# ARE_adaptadores_final.net
KiCad netlist of a schematic drawn in EAGLE
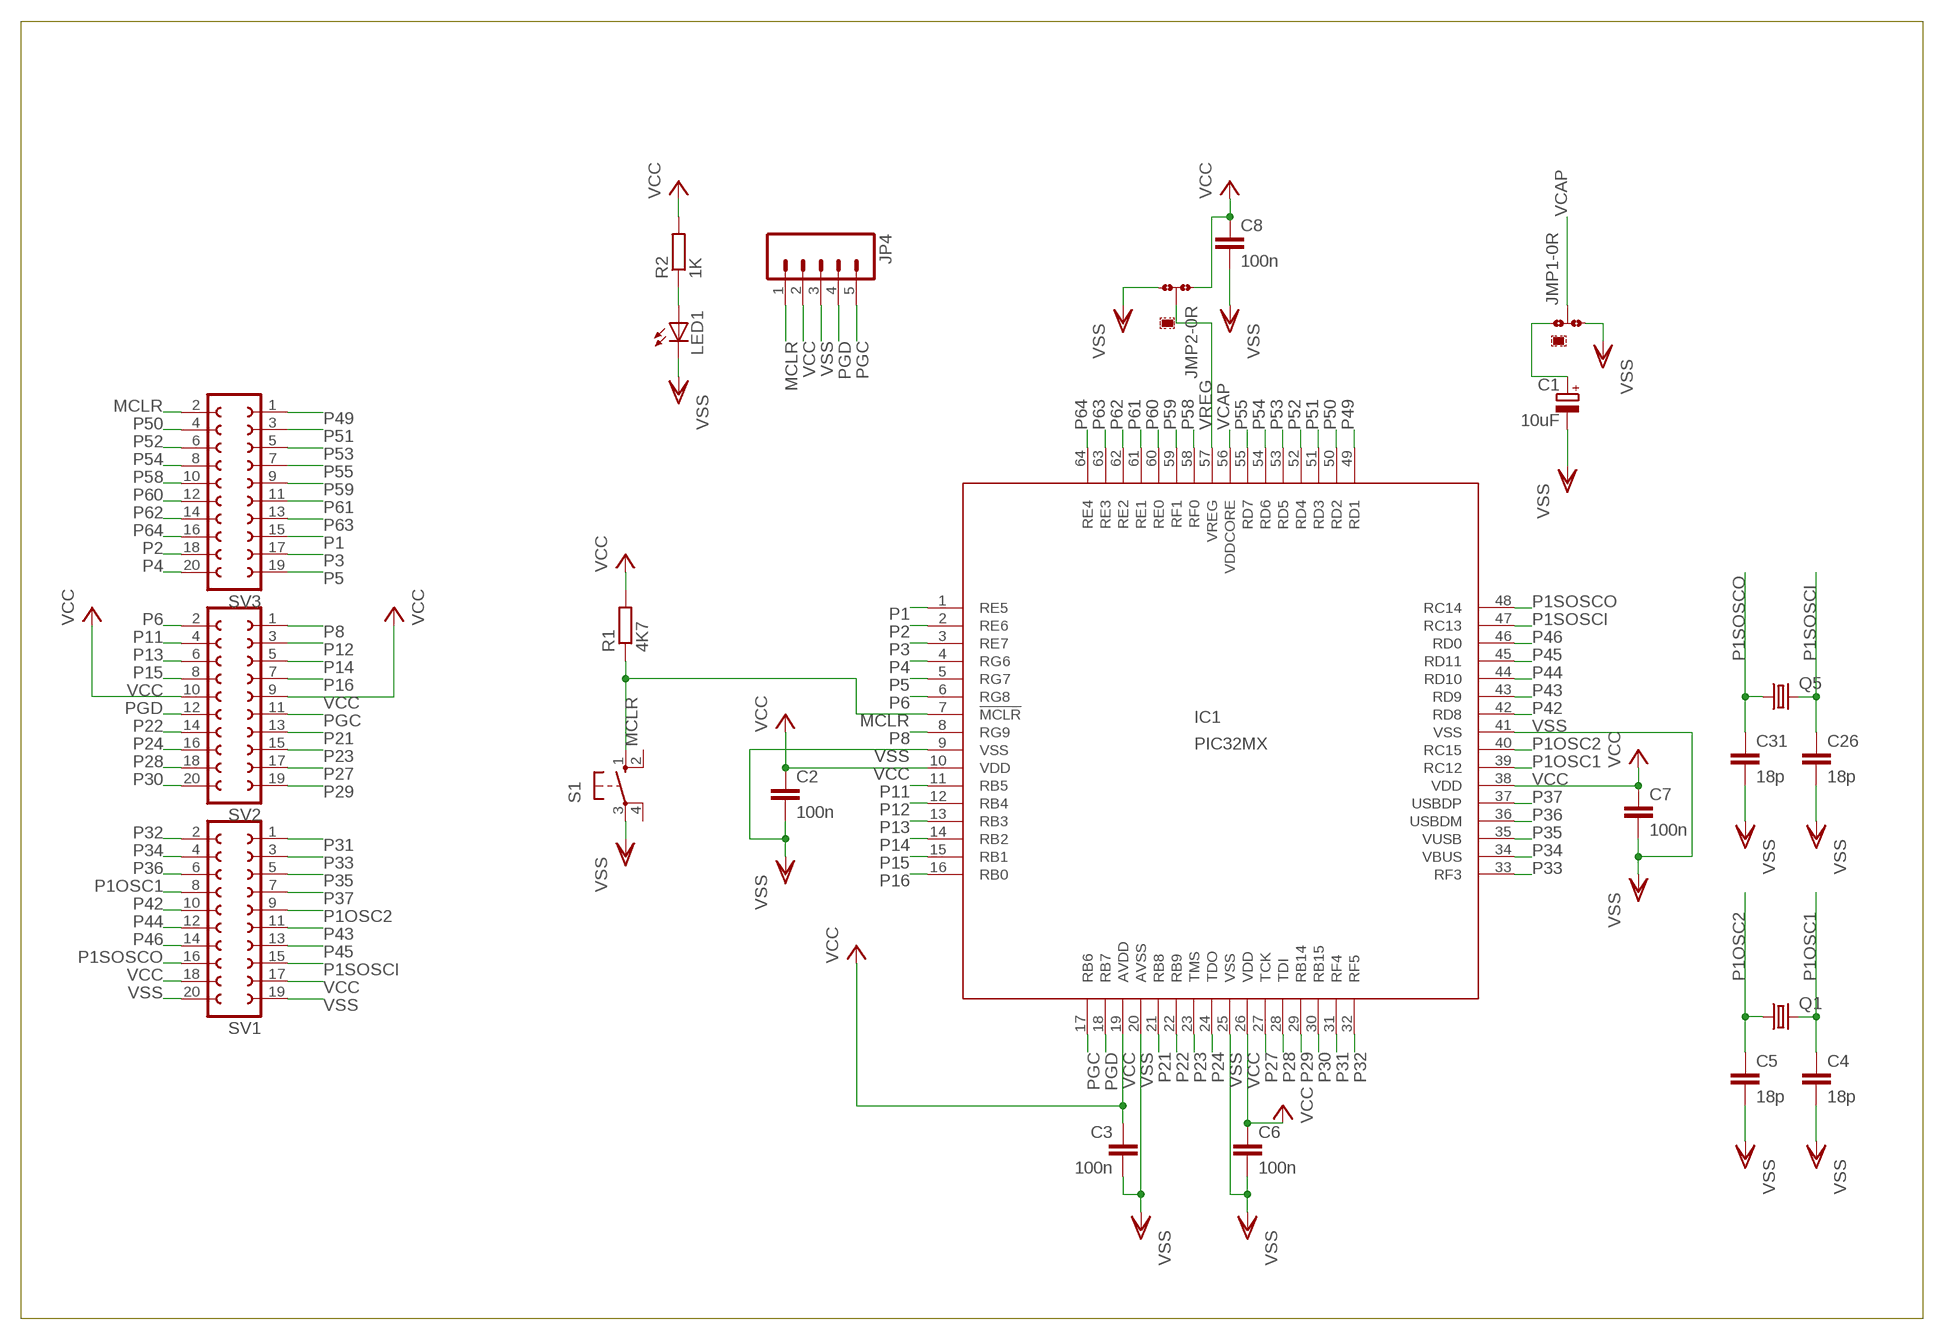
[diagram p0: schematic, sheet 1]
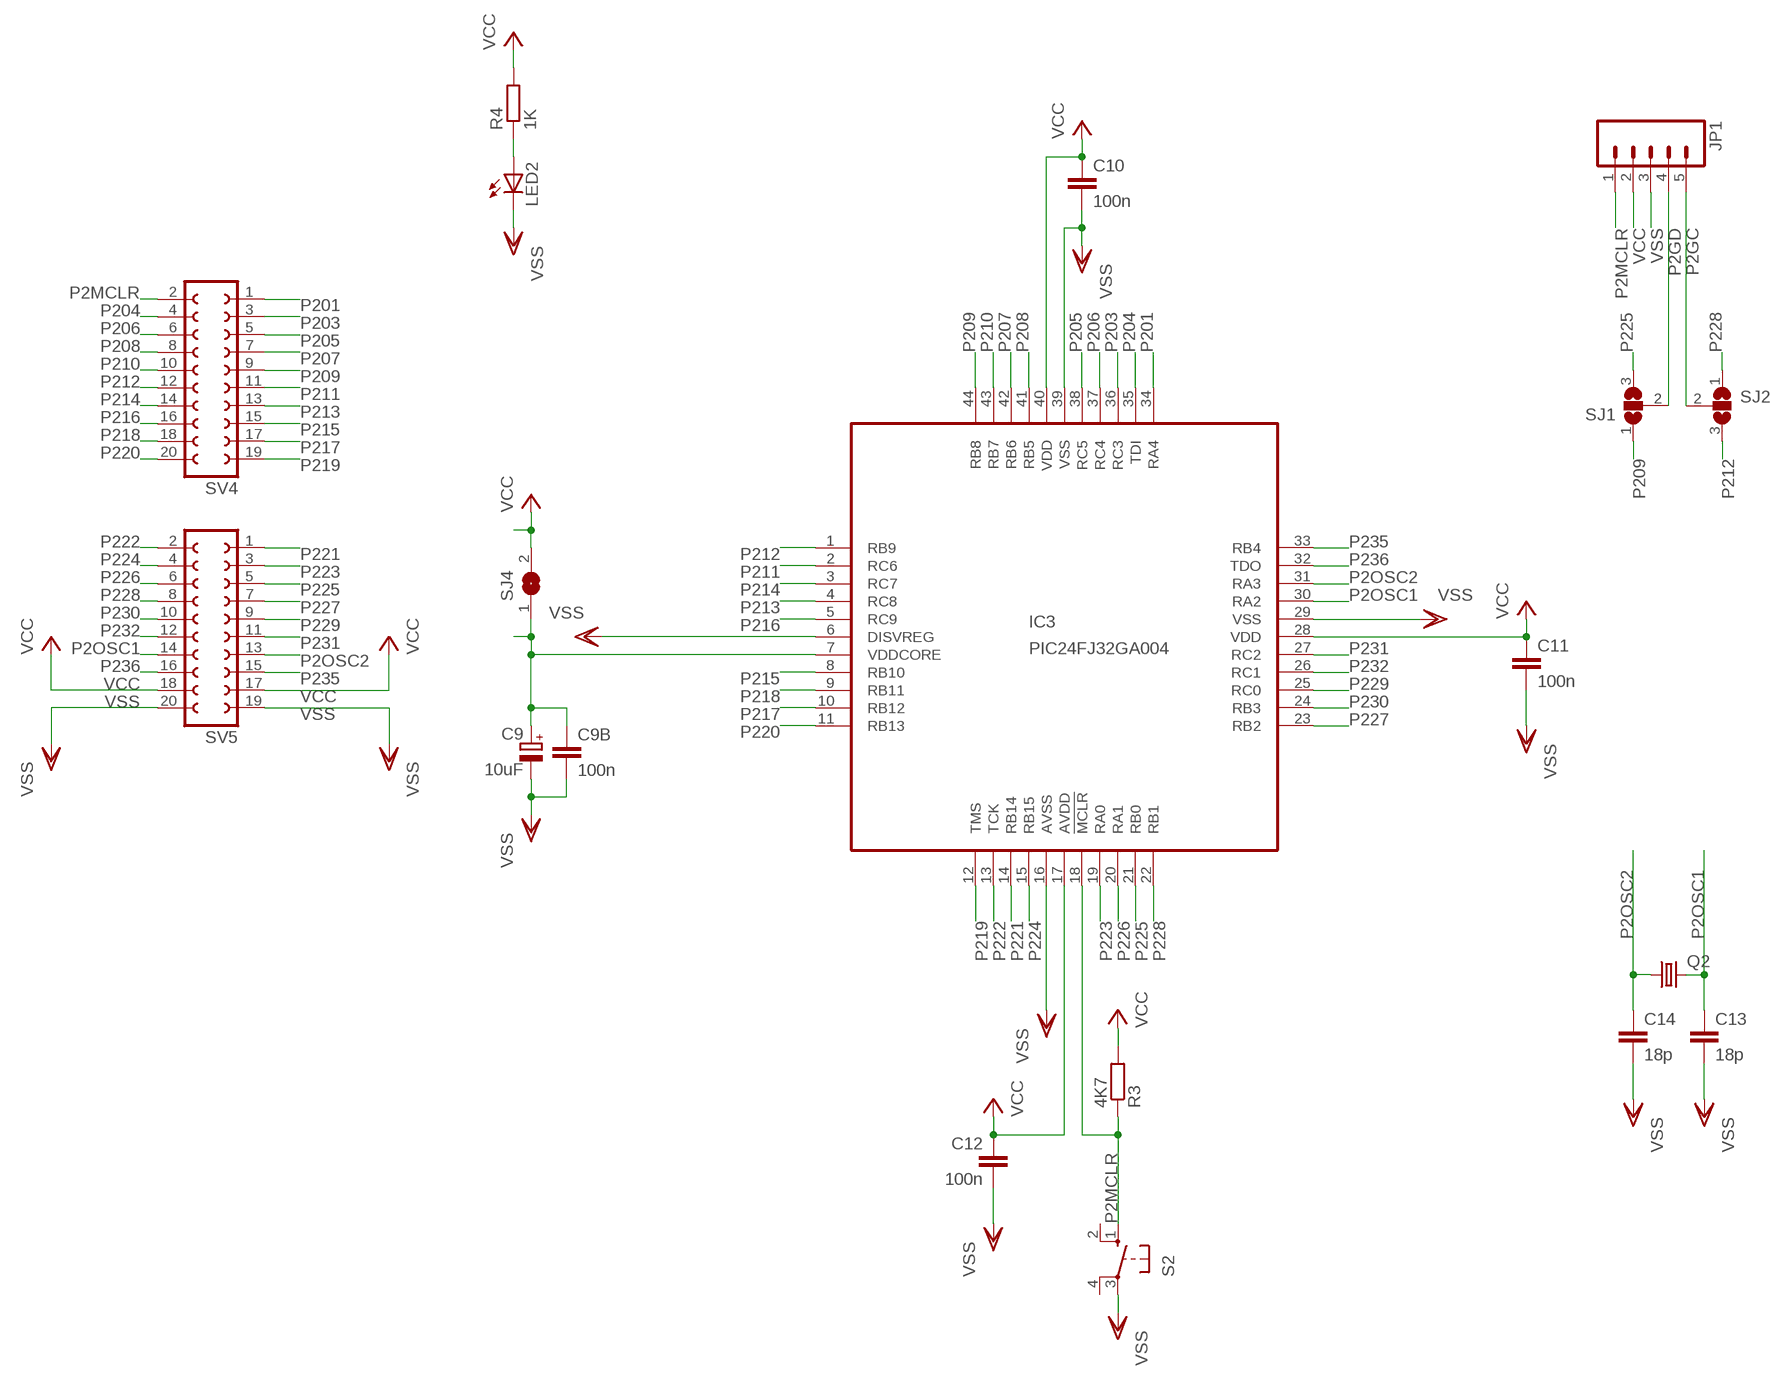
[diagram p1: schematic, sheet 2]
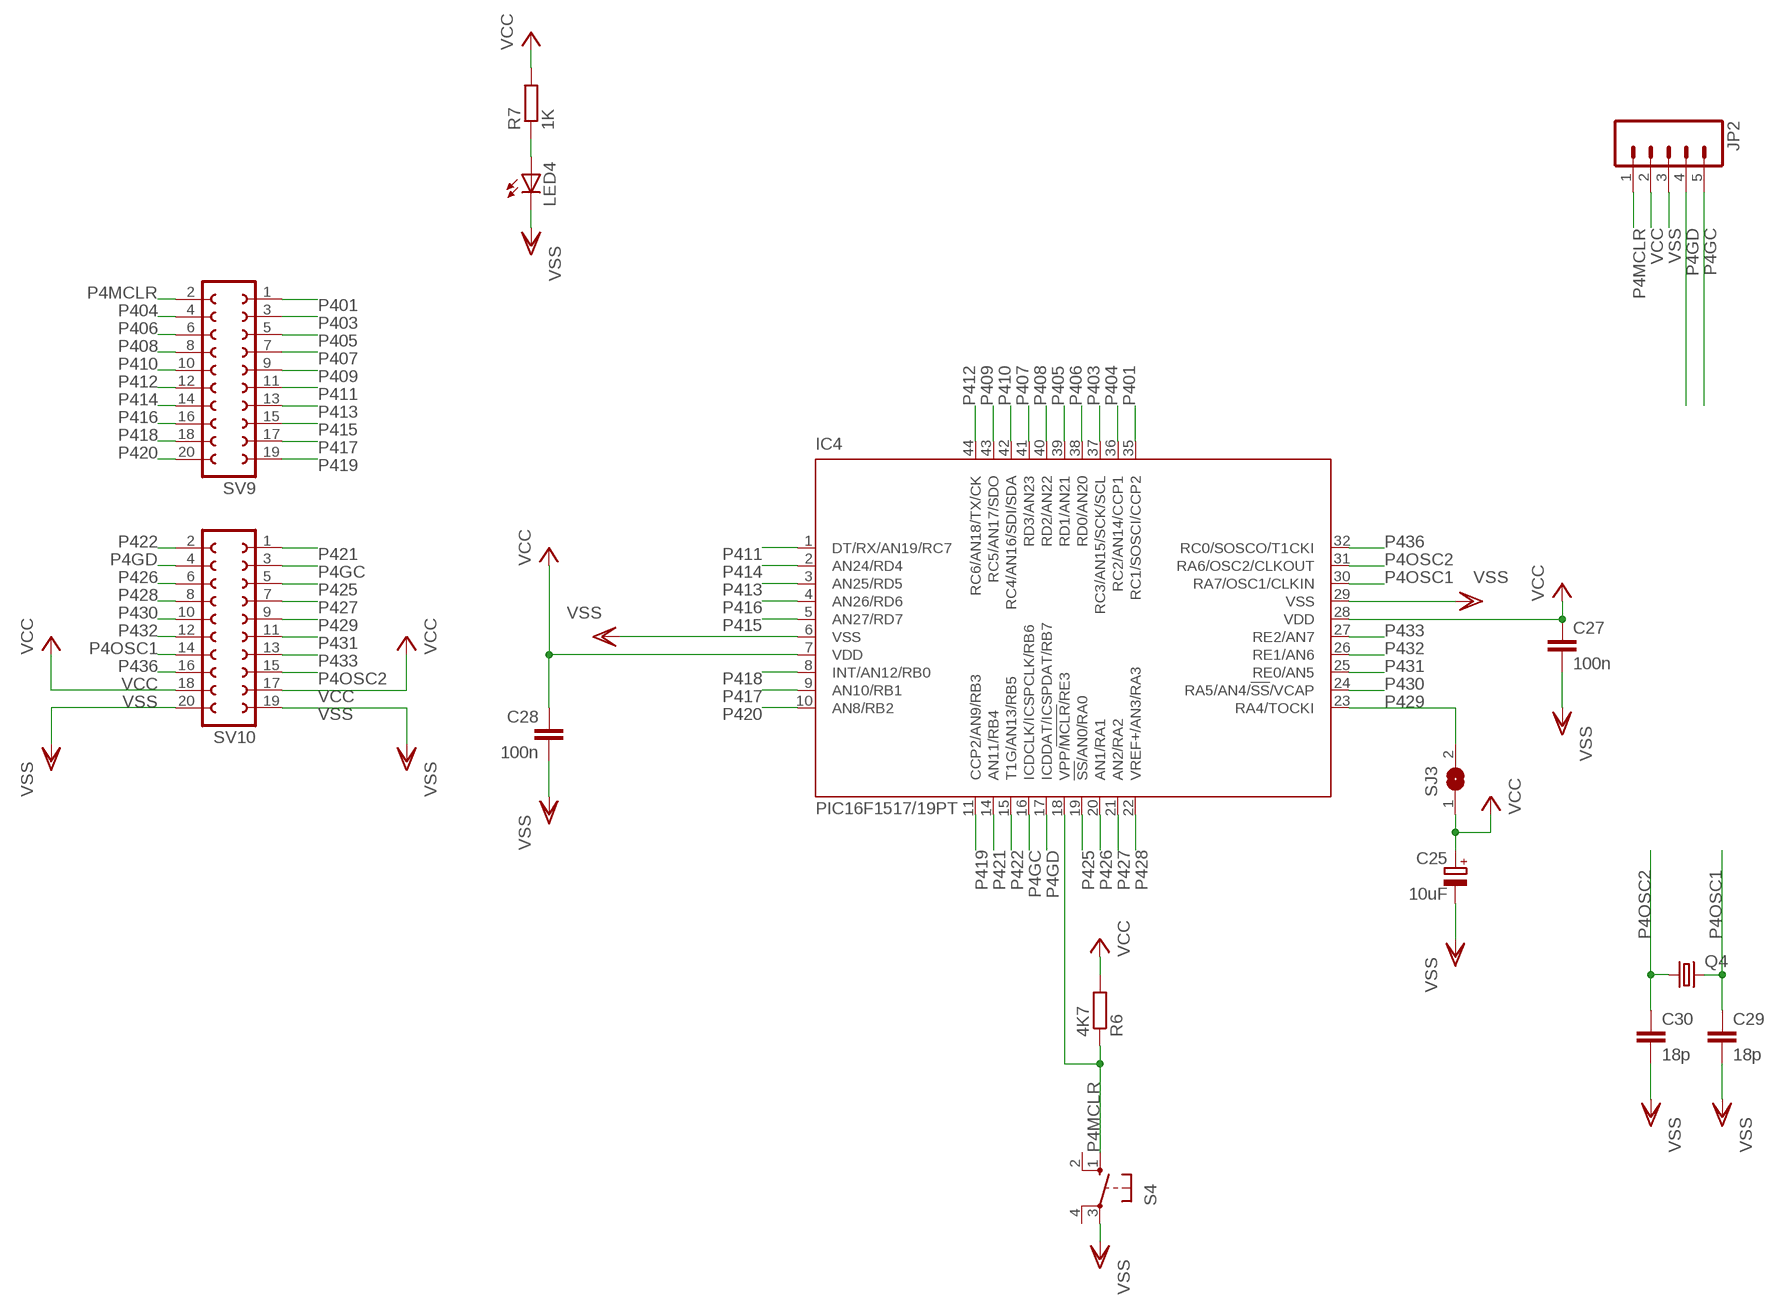
[diagram p2: schematic, sheet 3]
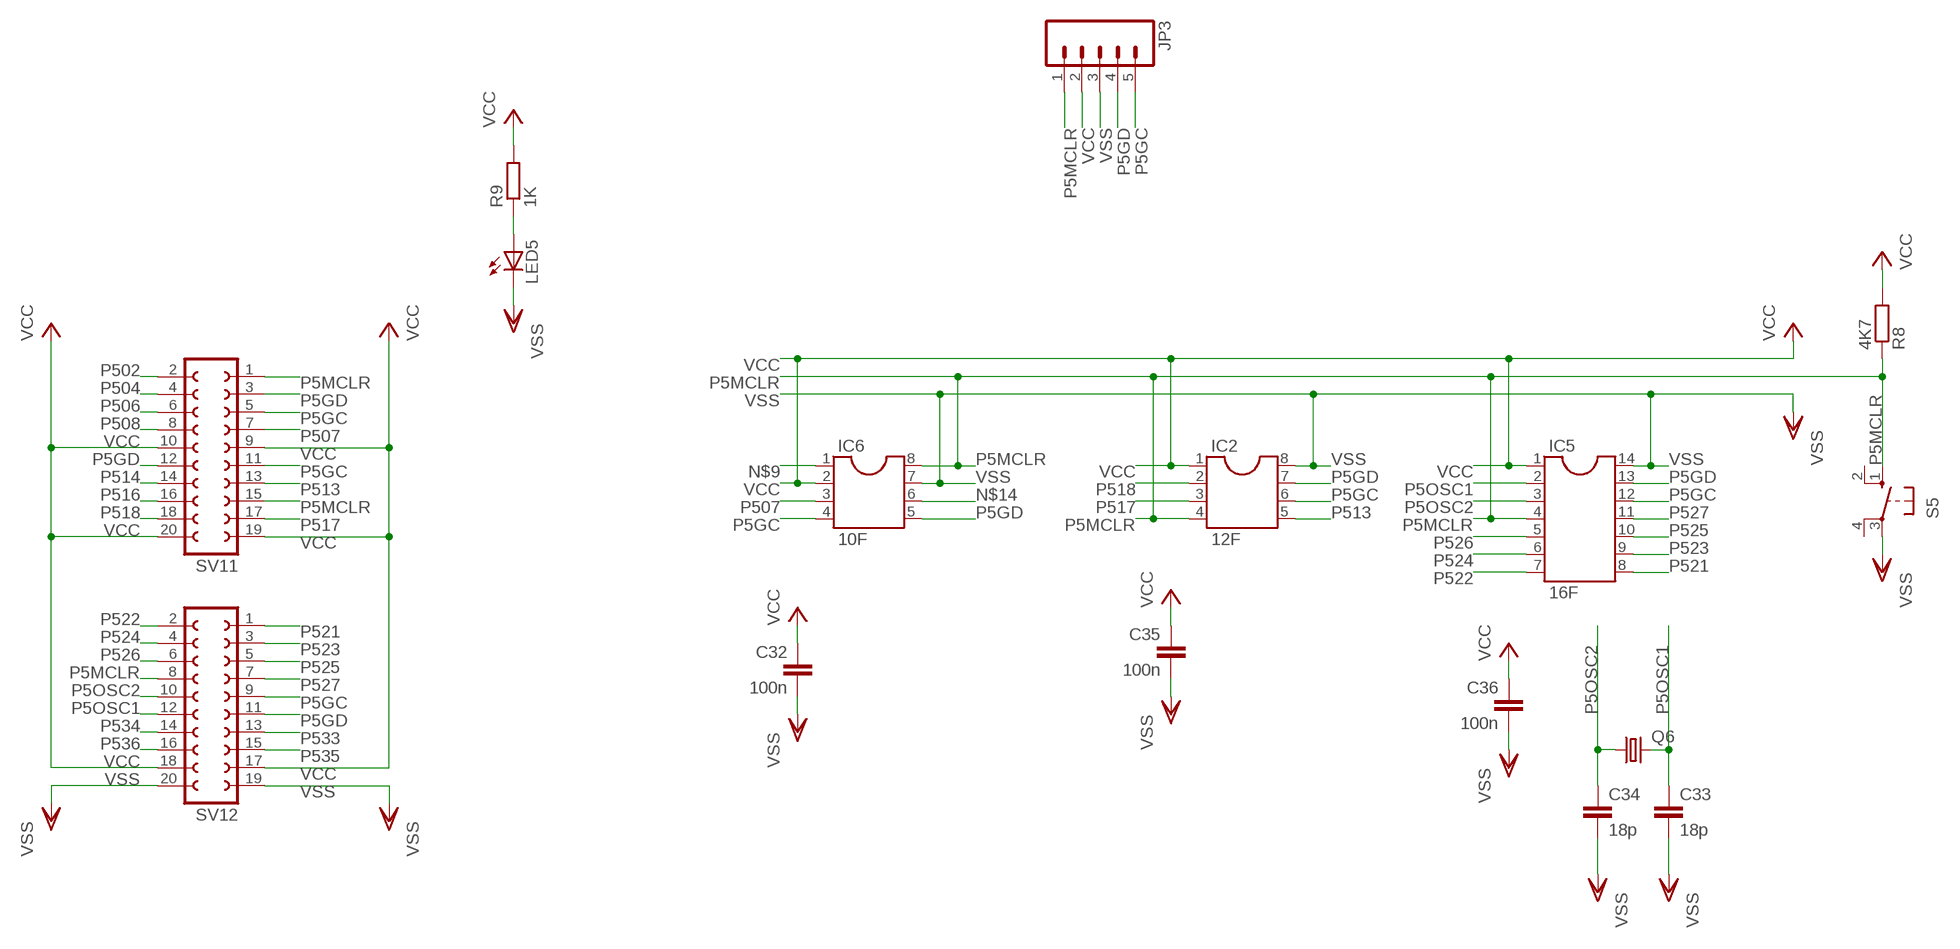
[diagram p3: schematic, sheet 4]

(export (version "E")
  (design (tool "Eeschema 10.0.6"))
  (components
    (comp (ref "C1")
      (value "10uF")
      (footprint "eagle-import:SMC_C")
      (libsource (lib "eagle-import") (part "CPOL-EUSMCC"))
    )
    (comp (ref "C2")
      (value "100n")
      (footprint "eagle-import:C0805")
      (libsource (lib "eagle-import") (part "C-EUC0805"))
    )
    (comp (ref "C3")
      (value "100n")
      (footprint "eagle-import:C0805")
      (libsource (lib "eagle-import") (part "C-EUC0805"))
    )
    (comp (ref "C4")
      (value "18p")
      (footprint "eagle-import:C0805")
      (libsource (lib "eagle-import") (part "C-EUC0805"))
    )
    (comp (ref "C5")
      (value "18p")
      (footprint "eagle-import:C0805")
      (libsource (lib "eagle-import") (part "C-EUC0805"))
    )
    (comp (ref "C6")
      (value "100n")
      (footprint "eagle-import:C0805")
      (libsource (lib "eagle-import") (part "C-EUC0805"))
    )
    (comp (ref "C7")
      (value "100n")
      (footprint "eagle-import:C0805")
      (libsource (lib "eagle-import") (part "C-EUC0805"))
    )
    (comp (ref "C8")
      (value "100n")
      (footprint "eagle-import:C0805")
      (libsource (lib "eagle-import") (part "C-EUC0805"))
    )
    (comp (ref "C26")
      (value "18p")
      (footprint "eagle-import:C0805")
      (libsource (lib "eagle-import") (part "C-EUC0805"))
    )
    (comp (ref "C31")
      (value "18p")
      (footprint "eagle-import:C0805")
      (libsource (lib "eagle-import") (part "C-EUC0805"))
    )
    (comp (ref "IC1")
      (value "PIC32MX")
      (footprint "eagle-import:TQFP64-10X10")
      (libsource (lib "eagle-import") (part "PIC32MX440F256H"))
    )
    (comp (ref "JMP1")
      (value "0R-JUMPA")
      (footprint "eagle-import:A0R-JMP")
      (libsource (lib "eagle-import") (part "0R-JUMPA"))
    )
    (comp (ref "JMP2")
      (value "0R-JUMPA")
      (footprint "eagle-import:A0R-JMP")
      (libsource (lib "eagle-import") (part "0R-JUMPA"))
    )
    (comp (ref "JP4")
      (value "M05PTH")
      (footprint "eagle-import:1X05")
      (libsource (lib "eagle-import") (part "M05PTH"))
    )
    (comp (ref "LED1")
      (value "LEDCHIPLED_0805")
      (footprint "eagle-import:CHIPLED_0805")
      (libsource (lib "eagle-import") (part "LEDCHIPLED_0805"))
    )
    (comp (ref "Q1")
      (value "CRYSTALHC18U-V")
      (footprint "eagle-import:HC18U-V")
      (libsource (lib "eagle-import") (part "CRYSTALHC18U-V"))
    )
    (comp (ref "Q5")
      (value "CRYSTALHC18U-V")
      (footprint "eagle-import:HC18U-V")
      (libsource (lib "eagle-import") (part "CRYSTALHC18U-V"))
    )
    (comp (ref "R1")
      (value "4K7")
      (footprint "eagle-import:R0805")
      (libsource (lib "eagle-import") (part "R-EU_R0805"))
    )
    (comp (ref "R2")
      (value "1K")
      (footprint "eagle-import:R0805")
      (libsource (lib "eagle-import") (part "R-EU_R0805"))
    )
    (comp (ref "S1")
      (value "10-XX")
      (footprint "eagle-import:B3F-10XX")
      (fields
        (field (name "MPN") "B3F-1000")
        (field (name "MPN_1") "B3F-1000")
        (field (name "OC_FARNELL") "176432")
        (field (name "OC_NEWARK") "36M3542")
      )
      (libsource (lib "eagle-import") (part "10-XX"))
    )
    (comp (ref "SV1")
      (value "FE10-2W")
      (footprint "eagle-import:FE10-2W")
      (libsource (lib "eagle-import") (part "FE10-2W"))
    )
    (comp (ref "SV2")
      (value "FE10-2W")
      (footprint "eagle-import:FE10-2W")
      (libsource (lib "eagle-import") (part "FE10-2W"))
    )
    (comp (ref "SV3")
      (value "FE10-2W")
      (footprint "eagle-import:FE10-2W")
      (libsource (lib "eagle-import") (part "FE10-2W"))
    )
    (comp (ref "C25")
      (value "10uF")
      (footprint "eagle-import:SMC_C")
      (libsource (lib "eagle-import") (part "CPOL-EUSMCC"))
    )
    (comp (ref "C27")
      (value "100n")
      (footprint "eagle-import:C0805")
      (libsource (lib "eagle-import") (part "C-EUC0805"))
    )
    (comp (ref "C28")
      (value "100n")
      (footprint "eagle-import:C0805")
      (libsource (lib "eagle-import") (part "C-EUC0805"))
    )
    (comp (ref "C29")
      (value "18p")
      (footprint "eagle-import:C0805")
      (libsource (lib "eagle-import") (part "C-EUC0805"))
    )
    (comp (ref "C30")
      (value "18p")
      (footprint "eagle-import:C0805")
      (libsource (lib "eagle-import") (part "C-EUC0805"))
    )
    (comp (ref "IC4")
      (value "PIC16F1517/19PT")
      (footprint "eagle-import:TQFP44")
      (libsource (lib "eagle-import") (part "PIC16F1517/19PT"))
    )
    (comp (ref "JP2")
      (value "M05PTH")
      (footprint "eagle-import:1X05")
      (libsource (lib "eagle-import") (part "M05PTH"))
    )
    (comp (ref "LED4")
      (value "LEDCHIPLED_0805")
      (footprint "eagle-import:CHIPLED_0805")
      (libsource (lib "eagle-import") (part "LEDCHIPLED_0805"))
    )
    (comp (ref "Q4")
      (value "CRYSTALHC18U-V")
      (footprint "eagle-import:HC18U-V")
      (libsource (lib "eagle-import") (part "CRYSTALHC18U-V"))
    )
    (comp (ref "R6")
      (value "4K7")
      (footprint "eagle-import:R0805")
      (libsource (lib "eagle-import") (part "R-EU_R0805"))
    )
    (comp (ref "R7")
      (value "1K")
      (footprint "eagle-import:R0805")
      (libsource (lib "eagle-import") (part "R-EU_R0805"))
    )
    (comp (ref "S4")
      (value "10-XX")
      (footprint "eagle-import:B3F-10XX")
      (fields
        (field (name "MPN") "B3F-1000")
        (field (name "MPN_1") "B3F-1000")
        (field (name "OC_FARNELL") "176432")
        (field (name "OC_NEWARK") "36M3542")
      )
      (libsource (lib "eagle-import") (part "10-XX"))
    )
    (comp (ref "SJ3") (value "SJ") (footprint "eagle-import:SJ") (libsource (lib "eagle-import") (part "SJ")))
    (comp (ref "SV9")
      (value "FE10-2W")
      (footprint "eagle-import:FE10-2W")
      (libsource (lib "eagle-import") (part "FE10-2W"))
    )
    (comp (ref "SV10")
      (value "FE10-2W")
      (footprint "eagle-import:FE10-2W")
      (libsource (lib "eagle-import") (part "FE10-2W"))
    )
    (comp (ref "C32")
      (value "100n")
      (footprint "eagle-import:C0805")
      (libsource (lib "eagle-import") (part "C-EUC0805"))
    )
    (comp (ref "C33")
      (value "18p")
      (footprint "eagle-import:C0805")
      (libsource (lib "eagle-import") (part "C-EUC0805"))
    )
    (comp (ref "C34")
      (value "18p")
      (footprint "eagle-import:C0805")
      (libsource (lib "eagle-import") (part "C-EUC0805"))
    )
    (comp (ref "C35")
      (value "100n")
      (footprint "eagle-import:C0805")
      (libsource (lib "eagle-import") (part "C-EUC0805"))
    )
    (comp (ref "C36")
      (value "100n")
      (footprint "eagle-import:C0805")
      (libsource (lib "eagle-import") (part "C-EUC0805"))
    )
    (comp (ref "IC2")
      (value "12F")
      (footprint "eagle-import:SOCKET-08")
      (libsource (lib "eagle-import") (part "DIL8S"))
    )
    (comp (ref "IC5")
      (value "16F")
      (footprint "eagle-import:SOCKET-14")
      (libsource (lib "eagle-import") (part "DIL14S"))
    )
    (comp (ref "IC6")
      (value "10F")
      (footprint "eagle-import:SOCKET-08")
      (libsource (lib "eagle-import") (part "DIL8S"))
    )
    (comp (ref "JP3")
      (value "M05PTH")
      (footprint "eagle-import:1X05")
      (libsource (lib "eagle-import") (part "M05PTH"))
    )
    (comp (ref "LED5")
      (value "LEDCHIPLED_0805")
      (footprint "eagle-import:CHIPLED_0805")
      (libsource (lib "eagle-import") (part "LEDCHIPLED_0805"))
    )
    (comp (ref "Q6")
      (value "CRYSTALHC18U-V")
      (footprint "eagle-import:HC18U-V")
      (libsource (lib "eagle-import") (part "CRYSTALHC18U-V"))
    )
    (comp (ref "R8")
      (value "4K7")
      (footprint "eagle-import:R0805")
      (libsource (lib "eagle-import") (part "R-EU_R0805"))
    )
    (comp (ref "R9")
      (value "1K")
      (footprint "eagle-import:R0805")
      (libsource (lib "eagle-import") (part "R-EU_R0805"))
    )
    (comp (ref "S5")
      (value "10-XX")
      (footprint "eagle-import:B3F-10XX")
      (fields
        (field (name "MPN") "B3F-1000")
        (field (name "MPN_1") "B3F-1000")
        (field (name "OC_FARNELL") "176432")
        (field (name "OC_NEWARK") "36M3542")
      )
      (libsource (lib "eagle-import") (part "10-XX"))
    )
    (comp (ref "SV11")
      (value "FE10-2W")
      (footprint "eagle-import:FE10-2W")
      (libsource (lib "eagle-import") (part "FE10-2W"))
    )
    (comp (ref "SV12")
      (value "FE10-2W")
      (footprint "eagle-import:FE10-2W")
      (libsource (lib "eagle-import") (part "FE10-2W"))
    )
    (comp (ref "C9")
      (value "10uF")
      (footprint "eagle-import:SMC_C")
      (libsource (lib "eagle-import") (part "CPOL-EUSMCC"))
    )
    (comp (ref "C9B")
      (value "100n")
      (footprint "eagle-import:C0805")
      (libsource (lib "eagle-import") (part "C-EUC0805"))
    )
    (comp (ref "C10")
      (value "100n")
      (footprint "eagle-import:C0805")
      (libsource (lib "eagle-import") (part "C-EUC0805"))
    )
    (comp (ref "C11")
      (value "100n")
      (footprint "eagle-import:C0805")
      (libsource (lib "eagle-import") (part "C-EUC0805"))
    )
    (comp (ref "C12")
      (value "100n")
      (footprint "eagle-import:C0805")
      (libsource (lib "eagle-import") (part "C-EUC0805"))
    )
    (comp (ref "C13")
      (value "18p")
      (footprint "eagle-import:C0805")
      (libsource (lib "eagle-import") (part "C-EUC0805"))
    )
    (comp (ref "C14")
      (value "18p")
      (footprint "eagle-import:C0805")
      (libsource (lib "eagle-import") (part "C-EUC0805"))
    )
    (comp (ref "IC3")
      (value "PIC24FJ32GA004")
      (footprint "eagle-import:TQFP44")
      (fields (field (name "MPN") "PIC24FJ32GA004-E/PT"))
      (libsource (lib "eagle-import") (part "PIC24FJ32GA004"))
    )
    (comp (ref "JP1")
      (value "M05PTH")
      (footprint "eagle-import:1X05")
      (libsource (lib "eagle-import") (part "M05PTH"))
    )
    (comp (ref "LED2")
      (value "LEDCHIPLED_0805")
      (footprint "eagle-import:CHIPLED_0805")
      (libsource (lib "eagle-import") (part "LEDCHIPLED_0805"))
    )
    (comp (ref "Q2")
      (value "CRYSTALHC18U-V")
      (footprint "eagle-import:HC18U-V")
      (libsource (lib "eagle-import") (part "CRYSTALHC18U-V"))
    )
    (comp (ref "R3")
      (value "4K7")
      (footprint "eagle-import:R0805")
      (libsource (lib "eagle-import") (part "R-EU_R0805"))
    )
    (comp (ref "R4")
      (value "1K")
      (footprint "eagle-import:R0805")
      (libsource (lib "eagle-import") (part "R-EU_R0805"))
    )
    (comp (ref "S2")
      (value "10-XX")
      (footprint "eagle-import:B3F-10XX")
      (fields
        (field (name "MPN") "B3F-1000")
        (field (name "MPN_1") "B3F-1000")
        (field (name "OC_FARNELL") "176432")
        (field (name "OC_NEWARK") "36M3542")
      )
      (libsource (lib "eagle-import") (part "10-XX"))
    )
    (comp (ref "SJ1")
      (value "SJ2W")
      (footprint "eagle-import:SJ_2")
      (libsource (lib "eagle-import") (part "SJ2W"))
    )
    (comp (ref "SJ2")
      (value "SJ2W")
      (footprint "eagle-import:SJ_2")
      (libsource (lib "eagle-import") (part "SJ2W"))
    )
    (comp (ref "SJ4") (value "SJ") (footprint "eagle-import:SJ") (libsource (lib "eagle-import") (part "SJ")))
    (comp (ref "SV4")
      (value "FE10-2W")
      (footprint "eagle-import:FE10-2W")
      (libsource (lib "eagle-import") (part "FE10-2W"))
    )
    (comp (ref "SV5")
      (value "FE10-2W")
      (footprint "eagle-import:FE10-2W")
      (libsource (lib "eagle-import") (part "FE10-2W"))
    )
  )
  (nets
    (net (code "1") (name "MCLR") (class "Default")
      (node (ref "IC1") (pin "7") (pinfunction "~{MCLR}_7") (pintype "input"))
      (node (ref "JP4") (pin "1") (pinfunction "1_1") (pintype "passive"))
      (node (ref "R1") (pin "1") (pinfunction "1_1") (pintype "passive"))
      (node (ref "S1") (pin "1") (pinfunction "S_1") (pintype "passive"))
      (node (ref "SV3") (pin "2") (pinfunction "2_2") (pintype "passive"))
    )
    (net (code "2") (name "N$9") (class "Default")
      (node (ref "IC6") (pin "1") (pinfunction "1_1") (pintype "passive"))
    )
    (net (code "3") (name "N$14") (class "Default")
      (node (ref "IC6") (pin "6") (pinfunction "6_6") (pintype "passive"))
    )
    (net (code "4") (name "Net-(C1-Pad+)") (class "Default")
      (node (ref "C1") (pin "+") (pinfunction "+_+") (pintype "passive"))
      (node (ref "JMP1") (pin "1") (pinfunction "1_1") (pintype "passive"))
    )
    (net (code "5") (name "Net-(IC3-VDDCORE)") (class "Default")
      (node (ref "C9") (pin "+") (pinfunction "+_+") (pintype "passive"))
      (node (ref "C9B") (pin "1") (pinfunction "1_1") (pintype "passive"))
      (node (ref "IC3") (pin "7") (pinfunction "VDDCORE_7") (pintype "power_in"))
      (node (ref "SJ4") (pin "1") (pinfunction "1_1") (pintype "passive"))
    )
    (net (code "6") (name "Net-(LED1-PadA)") (class "Default")
      (node (ref "LED1") (pin "A") (pinfunction "A_A") (pintype "passive"))
      (node (ref "R2") (pin "1") (pinfunction "1_1") (pintype "passive"))
    )
    (net (code "7") (name "Net-(LED2-PadA)") (class "Default")
      (node (ref "LED2") (pin "A") (pinfunction "A_A") (pintype "passive"))
      (node (ref "R4") (pin "1") (pinfunction "1_1") (pintype "passive"))
    )
    (net (code "8") (name "Net-(LED4-PadA)") (class "Default")
      (node (ref "LED4") (pin "A") (pinfunction "A_A") (pintype "passive"))
      (node (ref "R7") (pin "1") (pinfunction "1_1") (pintype "passive"))
    )
    (net (code "9") (name "Net-(LED5-PadA)") (class "Default")
      (node (ref "LED5") (pin "A") (pinfunction "A_A") (pintype "passive"))
      (node (ref "R9") (pin "1") (pinfunction "1_1") (pintype "passive"))
    )
    (net (code "10") (name "P1") (class "Default")
      (node (ref "IC1") (pin "1") (pinfunction "RE5_1") (pintype "bidirectional"))
      (node (ref "SV3") (pin "15") (pinfunction "15_15") (pintype "passive"))
    )
    (net (code "11") (name "P1OSC1") (class "Default")
      (node (ref "C4") (pin "1") (pinfunction "1_1") (pintype "passive"))
      (node (ref "IC1") (pin "39") (pinfunction "RC12_39") (pintype "bidirectional"))
      (node (ref "Q1") (pin "2") (pinfunction "2_2") (pintype "passive"))
      (node (ref "SV1") (pin "8") (pinfunction "8_8") (pintype "passive"))
    )
    (net (code "12") (name "P1OSC2") (class "Default")
      (node (ref "C5") (pin "1") (pinfunction "1_1") (pintype "passive"))
      (node (ref "IC1") (pin "40") (pinfunction "RC15_40") (pintype "bidirectional"))
      (node (ref "Q1") (pin "1") (pinfunction "1_1") (pintype "passive"))
      (node (ref "SV1") (pin "9") (pinfunction "9_9") (pintype "passive"))
    )
    (net (code "13") (name "P1SOSCI") (class "Default")
      (node (ref "C26") (pin "1") (pinfunction "1_1") (pintype "passive"))
      (node (ref "IC1") (pin "47") (pinfunction "RC13_47") (pintype "bidirectional"))
      (node (ref "Q5") (pin "2") (pinfunction "2_2") (pintype "passive"))
      (node (ref "SV1") (pin "15") (pinfunction "15_15") (pintype "passive"))
    )
    (net (code "14") (name "P1SOSCO") (class "Default")
      (node (ref "C31") (pin "1") (pinfunction "1_1") (pintype "passive"))
      (node (ref "IC1") (pin "48") (pinfunction "RC14_48") (pintype "bidirectional"))
      (node (ref "Q5") (pin "1") (pinfunction "1_1") (pintype "passive"))
      (node (ref "SV1") (pin "16") (pinfunction "16_16") (pintype "passive"))
    )
    (net (code "15") (name "P2") (class "Default")
      (node (ref "IC1") (pin "2") (pinfunction "RE6_2") (pintype "bidirectional"))
      (node (ref "SV3") (pin "18") (pinfunction "18_18") (pintype "passive"))
    )
    (net (code "16") (name "P2GC") (class "Default")
      (node (ref "JP1") (pin "5") (pinfunction "5_5") (pintype "passive"))
      (node (ref "SJ2") (pin "2") (pinfunction "2_2") (pintype "passive"))
    )
    (net (code "17") (name "P2GD") (class "Default")
      (node (ref "JP1") (pin "4") (pinfunction "4_4") (pintype "passive"))
      (node (ref "SJ1") (pin "2") (pinfunction "2_2") (pintype "passive"))
    )
    (net (code "18") (name "P2MCLR") (class "Default")
      (node (ref "IC3") (pin "18") (pinfunction "~{MCLR}_18") (pintype "bidirectional"))
      (node (ref "JP1") (pin "1") (pinfunction "1_1") (pintype "passive"))
      (node (ref "R3") (pin "1") (pinfunction "1_1") (pintype "passive"))
      (node (ref "S2") (pin "1") (pinfunction "S_1") (pintype "passive"))
      (node (ref "SV4") (pin "2") (pinfunction "2_2") (pintype "passive"))
    )
    (net (code "19") (name "P2OSC1") (class "Default")
      (node (ref "C13") (pin "1") (pinfunction "1_1") (pintype "passive"))
      (node (ref "IC3") (pin "30") (pinfunction "RA2_30") (pintype "bidirectional"))
      (node (ref "Q2") (pin "2") (pinfunction "2_2") (pintype "passive"))
      (node (ref "SV5") (pin "14") (pinfunction "14_14") (pintype "passive"))
    )
    (net (code "20") (name "P2OSC2") (class "Default")
      (node (ref "C14") (pin "1") (pinfunction "1_1") (pintype "passive"))
      (node (ref "IC3") (pin "31") (pinfunction "RA3_31") (pintype "bidirectional"))
      (node (ref "Q2") (pin "1") (pinfunction "1_1") (pintype "passive"))
      (node (ref "SV5") (pin "13") (pinfunction "13_13") (pintype "passive"))
    )
    (net (code "21") (name "P3") (class "Default")
      (node (ref "IC1") (pin "3") (pinfunction "RE7_3") (pintype "bidirectional"))
      (node (ref "SV3") (pin "17") (pinfunction "17_17") (pintype "passive"))
    )
    (net (code "22") (name "P4") (class "Default")
      (node (ref "IC1") (pin "4") (pinfunction "RG6_4") (pintype "bidirectional"))
      (node (ref "SV3") (pin "20") (pinfunction "20_20") (pintype "passive"))
    )
    (net (code "23") (name "P4GC") (class "Default")
      (node (ref "IC4") (pin "16") (pinfunction "ICDCLK/ICSPCLK/RB6_16") (pintype "bidirectional"))
      (node (ref "JP2") (pin "5") (pinfunction "5_5") (pintype "passive"))
      (node (ref "SV10") (pin "3") (pinfunction "3_3") (pintype "passive"))
    )
    (net (code "24") (name "P4GD") (class "Default")
      (node (ref "IC4") (pin "17") (pinfunction "ICDDAT/ICSPDAT/RB7_17") (pintype "bidirectional"))
      (node (ref "JP2") (pin "4") (pinfunction "4_4") (pintype "passive"))
      (node (ref "SV10") (pin "4") (pinfunction "4_4") (pintype "passive"))
    )
    (net (code "25") (name "P4MCLR") (class "Default")
      (node (ref "IC4") (pin "18") (pinfunction "VPP/~{MCLR}/RE3_18") (pintype "input"))
      (node (ref "JP2") (pin "1") (pinfunction "1_1") (pintype "passive"))
      (node (ref "R6") (pin "1") (pinfunction "1_1") (pintype "passive"))
      (node (ref "S4") (pin "1") (pinfunction "S_1") (pintype "passive"))
      (node (ref "SV9") (pin "2") (pinfunction "2_2") (pintype "passive"))
    )
    (net (code "26") (name "P4OSC1") (class "Default")
      (node (ref "C29") (pin "1") (pinfunction "1_1") (pintype "passive"))
      (node (ref "IC4") (pin "30") (pinfunction "RA7/OSC1/CLKIN_30") (pintype "bidirectional"))
      (node (ref "Q4") (pin "2") (pinfunction "2_2") (pintype "passive"))
      (node (ref "SV10") (pin "14") (pinfunction "14_14") (pintype "passive"))
    )
    (net (code "27") (name "P4OSC2") (class "Default")
      (node (ref "C30") (pin "1") (pinfunction "1_1") (pintype "passive"))
      (node (ref "IC4") (pin "31") (pinfunction "RA6/OSC2/CLKOUT_31") (pintype "bidirectional"))
      (node (ref "Q4") (pin "1") (pinfunction "1_1") (pintype "passive"))
      (node (ref "SV10") (pin "15") (pinfunction "15_15") (pintype "passive"))
    )
    (net (code "28") (name "P5") (class "Default")
      (node (ref "IC1") (pin "5") (pinfunction "RG7_5") (pintype "bidirectional"))
      (node (ref "SV3") (pin "19") (pinfunction "19_19") (pintype "passive"))
    )
    (net (code "29") (name "P5GC") (class "Default")
      (node (ref "IC2") (pin "6") (pinfunction "6_6") (pintype "passive"))
      (node (ref "IC5") (pin "12") (pinfunction "12_12") (pintype "passive"))
      (node (ref "IC6") (pin "4") (pinfunction "4_4") (pintype "passive"))
      (node (ref "JP3") (pin "5") (pinfunction "5_5") (pintype "passive"))
      (node (ref "SV11") (pin "11") (pinfunction "11_11") (pintype "passive"))
      (node (ref "SV11") (pin "5") (pinfunction "5_5") (pintype "passive"))
      (node (ref "SV12") (pin "9") (pinfunction "9_9") (pintype "passive"))
    )
    (net (code "30") (name "P5GD") (class "Default")
      (node (ref "IC2") (pin "7") (pinfunction "7_7") (pintype "passive"))
      (node (ref "IC5") (pin "13") (pinfunction "13_13") (pintype "passive"))
      (node (ref "IC6") (pin "5") (pinfunction "5_5") (pintype "passive"))
      (node (ref "JP3") (pin "4") (pinfunction "4_4") (pintype "passive"))
      (node (ref "SV11") (pin "12") (pinfunction "12_12") (pintype "passive"))
      (node (ref "SV11") (pin "3") (pinfunction "3_3") (pintype "passive"))
      (node (ref "SV12") (pin "11") (pinfunction "11_11") (pintype "passive"))
    )
    (net (code "31") (name "P5MCLR") (class "Default")
      (node (ref "IC2") (pin "4") (pinfunction "4_4") (pintype "passive"))
      (node (ref "IC5") (pin "4") (pinfunction "4_4") (pintype "passive"))
      (node (ref "IC6") (pin "8") (pinfunction "8_8") (pintype "passive"))
      (node (ref "JP3") (pin "1") (pinfunction "1_1") (pintype "passive"))
      (node (ref "R8") (pin "1") (pinfunction "1_1") (pintype "passive"))
      (node (ref "S5") (pin "1") (pinfunction "S_1") (pintype "passive"))
      (node (ref "SV11") (pin "1") (pinfunction "1_1") (pintype "passive"))
      (node (ref "SV11") (pin "15") (pinfunction "15_15") (pintype "passive"))
      (node (ref "SV12") (pin "8") (pinfunction "8_8") (pintype "passive"))
    )
    (net (code "32") (name "P5OSC1") (class "Default")
      (node (ref "C33") (pin "1") (pinfunction "1_1") (pintype "passive"))
      (node (ref "IC5") (pin "2") (pinfunction "2_2") (pintype "passive"))
      (node (ref "Q6") (pin "2") (pinfunction "2_2") (pintype "passive"))
      (node (ref "SV12") (pin "12") (pinfunction "12_12") (pintype "passive"))
    )
    (net (code "33") (name "P5OSC2") (class "Default")
      (node (ref "C34") (pin "1") (pinfunction "1_1") (pintype "passive"))
      (node (ref "IC5") (pin "3") (pinfunction "3_3") (pintype "passive"))
      (node (ref "Q6") (pin "1") (pinfunction "1_1") (pintype "passive"))
      (node (ref "SV12") (pin "10") (pinfunction "10_10") (pintype "passive"))
    )
    (net (code "34") (name "P6") (class "Default")
      (node (ref "IC1") (pin "6") (pinfunction "RG8_6") (pintype "bidirectional"))
      (node (ref "SV2") (pin "2") (pinfunction "2_2") (pintype "passive"))
    )
    (net (code "35") (name "P8") (class "Default")
      (node (ref "IC1") (pin "8") (pinfunction "RG9_8") (pintype "bidirectional"))
      (node (ref "SV2") (pin "1") (pinfunction "1_1") (pintype "passive"))
    )
    (net (code "36") (name "P11") (class "Default")
      (node (ref "IC1") (pin "11") (pinfunction "RB5_11") (pintype "bidirectional"))
      (node (ref "SV2") (pin "4") (pinfunction "4_4") (pintype "passive"))
    )
    (net (code "37") (name "P12") (class "Default")
      (node (ref "IC1") (pin "12") (pinfunction "RB4_12") (pintype "bidirectional"))
      (node (ref "SV2") (pin "3") (pinfunction "3_3") (pintype "passive"))
    )
    (net (code "38") (name "P13") (class "Default")
      (node (ref "IC1") (pin "13") (pinfunction "RB3_13") (pintype "bidirectional"))
      (node (ref "SV2") (pin "6") (pinfunction "6_6") (pintype "passive"))
    )
    (net (code "39") (name "P14") (class "Default")
      (node (ref "IC1") (pin "14") (pinfunction "RB2_14") (pintype "bidirectional"))
      (node (ref "SV2") (pin "5") (pinfunction "5_5") (pintype "passive"))
    )
    (net (code "40") (name "P15") (class "Default")
      (node (ref "IC1") (pin "15") (pinfunction "RB1_15") (pintype "bidirectional"))
      (node (ref "SV2") (pin "8") (pinfunction "8_8") (pintype "passive"))
    )
    (net (code "41") (name "P16") (class "Default")
      (node (ref "IC1") (pin "16") (pinfunction "RB0_16") (pintype "bidirectional"))
      (node (ref "SV2") (pin "7") (pinfunction "7_7") (pintype "passive"))
    )
    (net (code "42") (name "P21") (class "Default")
      (node (ref "IC1") (pin "21") (pinfunction "RB8_21") (pintype "bidirectional"))
      (node (ref "SV2") (pin "13") (pinfunction "13_13") (pintype "passive"))
    )
    (net (code "43") (name "P22") (class "Default")
      (node (ref "IC1") (pin "22") (pinfunction "RB9_22") (pintype "bidirectional"))
      (node (ref "SV2") (pin "14") (pinfunction "14_14") (pintype "passive"))
    )
    (net (code "44") (name "P23") (class "Default")
      (node (ref "IC1") (pin "23") (pinfunction "TMS_23") (pintype "input"))
      (node (ref "SV2") (pin "15") (pinfunction "15_15") (pintype "passive"))
    )
    (net (code "45") (name "P24") (class "Default")
      (node (ref "IC1") (pin "24") (pinfunction "TDO_24") (pintype "output"))
      (node (ref "SV2") (pin "16") (pinfunction "16_16") (pintype "passive"))
    )
    (net (code "46") (name "P27") (class "Default")
      (node (ref "IC1") (pin "27") (pinfunction "TCK_27") (pintype "input"))
      (node (ref "SV2") (pin "17") (pinfunction "17_17") (pintype "passive"))
    )
    (net (code "47") (name "P28") (class "Default")
      (node (ref "IC1") (pin "28") (pinfunction "TDI_28") (pintype "input"))
      (node (ref "SV2") (pin "18") (pinfunction "18_18") (pintype "passive"))
    )
    (net (code "48") (name "P29") (class "Default")
      (node (ref "IC1") (pin "29") (pinfunction "RB14_29") (pintype "bidirectional"))
      (node (ref "SV2") (pin "19") (pinfunction "19_19") (pintype "passive"))
    )
    (net (code "49") (name "P30") (class "Default")
      (node (ref "IC1") (pin "30") (pinfunction "RB15_30") (pintype "bidirectional"))
      (node (ref "SV2") (pin "20") (pinfunction "20_20") (pintype "passive"))
    )
    (net (code "50") (name "P31") (class "Default")
      (node (ref "IC1") (pin "31") (pinfunction "RF4_31") (pintype "bidirectional"))
      (node (ref "SV1") (pin "1") (pinfunction "1_1") (pintype "passive"))
    )
    (net (code "51") (name "P32") (class "Default")
      (node (ref "IC1") (pin "32") (pinfunction "RF5_32") (pintype "bidirectional"))
      (node (ref "SV1") (pin "2") (pinfunction "2_2") (pintype "passive"))
    )
    (net (code "52") (name "P33") (class "Default")
      (node (ref "IC1") (pin "33") (pinfunction "RF3_33") (pintype "bidirectional"))
      (node (ref "SV1") (pin "3") (pinfunction "3_3") (pintype "passive"))
    )
    (net (code "53") (name "P34") (class "Default")
      (node (ref "IC1") (pin "34") (pinfunction "VBUS_34") (pintype "bidirectional"))
      (node (ref "SV1") (pin "4") (pinfunction "4_4") (pintype "passive"))
    )
    (net (code "54") (name "P35") (class "Default")
      (node (ref "IC1") (pin "35") (pinfunction "VUSB_35") (pintype "passive"))
      (node (ref "SV1") (pin "5") (pinfunction "5_5") (pintype "passive"))
    )
    (net (code "55") (name "P36") (class "Default")
      (node (ref "IC1") (pin "36") (pinfunction "USBDM_36") (pintype "bidirectional"))
      (node (ref "SV1") (pin "6") (pinfunction "6_6") (pintype "passive"))
    )
    (net (code "56") (name "P37") (class "Default")
      (node (ref "IC1") (pin "37") (pinfunction "USBDP_37") (pintype "bidirectional"))
      (node (ref "SV1") (pin "7") (pinfunction "7_7") (pintype "passive"))
    )
    (net (code "57") (name "P42") (class "Default")
      (node (ref "IC1") (pin "42") (pinfunction "RD8_42") (pintype "bidirectional"))
      (node (ref "SV1") (pin "10") (pinfunction "10_10") (pintype "passive"))
    )
    (net (code "58") (name "P43") (class "Default")
      (node (ref "IC1") (pin "43") (pinfunction "RD9_43") (pintype "bidirectional"))
      (node (ref "SV1") (pin "11") (pinfunction "11_11") (pintype "passive"))
    )
    (net (code "59") (name "P44") (class "Default")
      (node (ref "IC1") (pin "44") (pinfunction "RD10_44") (pintype "bidirectional"))
      (node (ref "SV1") (pin "12") (pinfunction "12_12") (pintype "passive"))
    )
    (net (code "60") (name "P45") (class "Default")
      (node (ref "IC1") (pin "45") (pinfunction "RD11_45") (pintype "bidirectional"))
      (node (ref "SV1") (pin "13") (pinfunction "13_13") (pintype "passive"))
    )
    (net (code "61") (name "P46") (class "Default")
      (node (ref "IC1") (pin "46") (pinfunction "RD0_46") (pintype "bidirectional"))
      (node (ref "SV1") (pin "14") (pinfunction "14_14") (pintype "passive"))
    )
    (net (code "62") (name "P49") (class "Default")
      (node (ref "IC1") (pin "49") (pinfunction "RD1_49") (pintype "bidirectional"))
      (node (ref "SV3") (pin "1") (pinfunction "1_1") (pintype "passive"))
    )
    (net (code "63") (name "P50") (class "Default")
      (node (ref "IC1") (pin "50") (pinfunction "RD2_50") (pintype "bidirectional"))
      (node (ref "SV3") (pin "4") (pinfunction "4_4") (pintype "passive"))
    )
    (net (code "64") (name "P51") (class "Default")
      (node (ref "IC1") (pin "51") (pinfunction "RD3_51") (pintype "bidirectional"))
      (node (ref "SV3") (pin "3") (pinfunction "3_3") (pintype "passive"))
    )
    (net (code "65") (name "P52") (class "Default")
      (node (ref "IC1") (pin "52") (pinfunction "RD4_52") (pintype "bidirectional"))
      (node (ref "SV3") (pin "6") (pinfunction "6_6") (pintype "passive"))
    )
    (net (code "66") (name "P53") (class "Default")
      (node (ref "IC1") (pin "53") (pinfunction "RD5_53") (pintype "bidirectional"))
      (node (ref "SV3") (pin "5") (pinfunction "5_5") (pintype "passive"))
    )
    (net (code "67") (name "P54") (class "Default")
      (node (ref "IC1") (pin "54") (pinfunction "RD6_54") (pintype "bidirectional"))
      (node (ref "SV3") (pin "8") (pinfunction "8_8") (pintype "passive"))
    )
    (net (code "68") (name "P55") (class "Default")
      (node (ref "IC1") (pin "55") (pinfunction "RD7_55") (pintype "bidirectional"))
      (node (ref "SV3") (pin "7") (pinfunction "7_7") (pintype "passive"))
    )
    (net (code "69") (name "P58") (class "Default")
      (node (ref "IC1") (pin "58") (pinfunction "RF0_58") (pintype "bidirectional"))
      (node (ref "SV3") (pin "10") (pinfunction "10_10") (pintype "passive"))
    )
    (net (code "70") (name "P59") (class "Default")
      (node (ref "IC1") (pin "59") (pinfunction "RF1_59") (pintype "bidirectional"))
      (node (ref "SV3") (pin "9") (pinfunction "9_9") (pintype "passive"))
    )
    (net (code "71") (name "P60") (class "Default")
      (node (ref "IC1") (pin "60") (pinfunction "RE0_60") (pintype "bidirectional"))
      (node (ref "SV3") (pin "12") (pinfunction "12_12") (pintype "passive"))
    )
    (net (code "72") (name "P61") (class "Default")
      (node (ref "IC1") (pin "61") (pinfunction "RE1_61") (pintype "bidirectional"))
      (node (ref "SV3") (pin "11") (pinfunction "11_11") (pintype "passive"))
    )
    (net (code "73") (name "P62") (class "Default")
      (node (ref "IC1") (pin "62") (pinfunction "RE2_62") (pintype "bidirectional"))
      (node (ref "SV3") (pin "14") (pinfunction "14_14") (pintype "passive"))
    )
    (net (code "74") (name "P63") (class "Default")
      (node (ref "IC1") (pin "63") (pinfunction "RE3_63") (pintype "bidirectional"))
      (node (ref "SV3") (pin "13") (pinfunction "13_13") (pintype "passive"))
    )
    (net (code "75") (name "P64") (class "Default")
      (node (ref "IC1") (pin "64") (pinfunction "RE4_64") (pintype "bidirectional"))
      (node (ref "SV3") (pin "16") (pinfunction "16_16") (pintype "passive"))
    )
    (net (code "76") (name "P201") (class "Default")
      (node (ref "IC3") (pin "34") (pinfunction "RA4_34") (pintype "bidirectional"))
      (node (ref "SV4") (pin "1") (pinfunction "1_1") (pintype "passive"))
    )
    (net (code "77") (name "P203") (class "Default")
      (node (ref "IC3") (pin "36") (pinfunction "RC3_36") (pintype "bidirectional"))
      (node (ref "SV4") (pin "3") (pinfunction "3_3") (pintype "passive"))
    )
    (net (code "78") (name "P204") (class "Default")
      (node (ref "IC3") (pin "35") (pinfunction "TDI_35") (pintype "input"))
      (node (ref "SV4") (pin "4") (pinfunction "4_4") (pintype "passive"))
    )
    (net (code "79") (name "P205") (class "Default")
      (node (ref "IC3") (pin "38") (pinfunction "RC5_38") (pintype "bidirectional"))
      (node (ref "SV4") (pin "5") (pinfunction "5_5") (pintype "passive"))
    )
    (net (code "80") (name "P206") (class "Default")
      (node (ref "IC3") (pin "37") (pinfunction "RC4_37") (pintype "bidirectional"))
      (node (ref "SV4") (pin "6") (pinfunction "6_6") (pintype "passive"))
    )
    (net (code "81") (name "P207") (class "Default")
      (node (ref "IC3") (pin "42") (pinfunction "RB6_42") (pintype "bidirectional"))
      (node (ref "SV4") (pin "7") (pinfunction "7_7") (pintype "passive"))
    )
    (net (code "82") (name "P208") (class "Default")
      (node (ref "IC3") (pin "41") (pinfunction "RB5_41") (pintype "bidirectional"))
      (node (ref "SV4") (pin "8") (pinfunction "8_8") (pintype "passive"))
    )
    (net (code "83") (name "P209") (class "Default")
      (node (ref "IC3") (pin "44") (pinfunction "RB8_44") (pintype "bidirectional"))
      (node (ref "SJ1") (pin "1") (pinfunction "1_1") (pintype "passive"))
      (node (ref "SV4") (pin "9") (pinfunction "9_9") (pintype "passive"))
    )
    (net (code "84") (name "P210") (class "Default")
      (node (ref "IC3") (pin "43") (pinfunction "RB7_43") (pintype "bidirectional"))
      (node (ref "SV4") (pin "10") (pinfunction "10_10") (pintype "passive"))
    )
    (net (code "85") (name "P211") (class "Default")
      (node (ref "IC3") (pin "2") (pinfunction "RC6_2") (pintype "bidirectional"))
      (node (ref "SV4") (pin "11") (pinfunction "11_11") (pintype "passive"))
    )
    (net (code "86") (name "P212") (class "Default")
      (node (ref "IC3") (pin "1") (pinfunction "RB9_1") (pintype "bidirectional"))
      (node (ref "SJ2") (pin "3") (pinfunction "3_3") (pintype "passive"))
      (node (ref "SV4") (pin "12") (pinfunction "12_12") (pintype "passive"))
    )
    (net (code "87") (name "P213") (class "Default")
      (node (ref "IC3") (pin "4") (pinfunction "RC8_4") (pintype "bidirectional"))
      (node (ref "SV4") (pin "13") (pinfunction "13_13") (pintype "passive"))
    )
    (net (code "88") (name "P214") (class "Default")
      (node (ref "IC3") (pin "3") (pinfunction "RC7_3") (pintype "bidirectional"))
      (node (ref "SV4") (pin "14") (pinfunction "14_14") (pintype "passive"))
    )
    (net (code "89") (name "P215") (class "Default")
      (node (ref "IC3") (pin "8") (pinfunction "RB10_8") (pintype "bidirectional"))
      (node (ref "SV4") (pin "15") (pinfunction "15_15") (pintype "passive"))
    )
    (net (code "90") (name "P216") (class "Default")
      (node (ref "IC3") (pin "5") (pinfunction "RC9_5") (pintype "bidirectional"))
      (node (ref "SV4") (pin "16") (pinfunction "16_16") (pintype "passive"))
    )
    (net (code "91") (name "P217") (class "Default")
      (node (ref "IC3") (pin "10") (pinfunction "RB12_10") (pintype "bidirectional"))
      (node (ref "SV4") (pin "17") (pinfunction "17_17") (pintype "passive"))
    )
    (net (code "92") (name "P218") (class "Default")
      (node (ref "IC3") (pin "9") (pinfunction "RB11_9") (pintype "bidirectional"))
      (node (ref "SV4") (pin "18") (pinfunction "18_18") (pintype "passive"))
    )
    (net (code "93") (name "P219") (class "Default")
      (node (ref "IC3") (pin "12") (pinfunction "TMS_12") (pintype "input"))
      (node (ref "SV4") (pin "19") (pinfunction "19_19") (pintype "passive"))
    )
    (net (code "94") (name "P220") (class "Default")
      (node (ref "IC3") (pin "11") (pinfunction "RB13_11") (pintype "bidirectional"))
      (node (ref "SV4") (pin "20") (pinfunction "20_20") (pintype "passive"))
    )
    (net (code "95") (name "P221") (class "Default")
      (node (ref "IC3") (pin "14") (pinfunction "RB14_14") (pintype "bidirectional"))
      (node (ref "SV5") (pin "1") (pinfunction "1_1") (pintype "passive"))
    )
    (net (code "96") (name "P222") (class "Default")
      (node (ref "IC3") (pin "13") (pinfunction "TCK_13") (pintype "input"))
      (node (ref "SV5") (pin "2") (pinfunction "2_2") (pintype "passive"))
    )
    (net (code "97") (name "P223") (class "Default")
      (node (ref "IC3") (pin "19") (pinfunction "RA0_19") (pintype "bidirectional"))
      (node (ref "SV5") (pin "3") (pinfunction "3_3") (pintype "passive"))
    )
    (net (code "98") (name "P224") (class "Default")
      (node (ref "IC3") (pin "15") (pinfunction "RB15_15") (pintype "bidirectional"))
      (node (ref "SV5") (pin "4") (pinfunction "4_4") (pintype "passive"))
    )
    (net (code "99") (name "P225") (class "Default")
      (node (ref "IC3") (pin "21") (pinfunction "RB0_21") (pintype "bidirectional"))
      (node (ref "SJ1") (pin "3") (pinfunction "3_3") (pintype "passive"))
      (node (ref "SV5") (pin "5") (pinfunction "5_5") (pintype "passive"))
    )
    (net (code "100") (name "P226") (class "Default")
      (node (ref "IC3") (pin "20") (pinfunction "RA1_20") (pintype "bidirectional"))
      (node (ref "SV5") (pin "6") (pinfunction "6_6") (pintype "passive"))
    )
    (net (code "101") (name "P227") (class "Default")
      (node (ref "IC3") (pin "23") (pinfunction "RB2_23") (pintype "bidirectional"))
      (node (ref "SV5") (pin "7") (pinfunction "7_7") (pintype "passive"))
    )
    (net (code "102") (name "P228") (class "Default")
      (node (ref "IC3") (pin "22") (pinfunction "RB1_22") (pintype "bidirectional"))
      (node (ref "SJ2") (pin "1") (pinfunction "1_1") (pintype "passive"))
      (node (ref "SV5") (pin "8") (pinfunction "8_8") (pintype "passive"))
    )
    (net (code "103") (name "P229") (class "Default")
      (node (ref "IC3") (pin "25") (pinfunction "RC0_25") (pintype "bidirectional"))
      (node (ref "SV5") (pin "9") (pinfunction "9_9") (pintype "passive"))
    )
    (net (code "104") (name "P230") (class "Default")
      (node (ref "IC3") (pin "24") (pinfunction "RB3_24") (pintype "bidirectional"))
      (node (ref "SV5") (pin "10") (pinfunction "10_10") (pintype "passive"))
    )
    (net (code "105") (name "P231") (class "Default")
      (node (ref "IC3") (pin "27") (pinfunction "RC2_27") (pintype "bidirectional"))
      (node (ref "SV5") (pin "11") (pinfunction "11_11") (pintype "passive"))
    )
    (net (code "106") (name "P232") (class "Default")
      (node (ref "IC3") (pin "26") (pinfunction "RC1_26") (pintype "bidirectional"))
      (node (ref "SV5") (pin "12") (pinfunction "12_12") (pintype "passive"))
    )
    (net (code "107") (name "P235") (class "Default")
      (node (ref "IC3") (pin "33") (pinfunction "RB4_33") (pintype "bidirectional"))
      (node (ref "SV5") (pin "15") (pinfunction "15_15") (pintype "passive"))
    )
    (net (code "108") (name "P236") (class "Default")
      (node (ref "IC3") (pin "32") (pinfunction "TDO_32") (pintype "output"))
      (node (ref "SV5") (pin "16") (pinfunction "16_16") (pintype "passive"))
    )
    (net (code "109") (name "P401") (class "Default")
      (node (ref "IC4") (pin "35") (pinfunction "RC1/SOSCI/CCP2_35") (pintype "bidirectional"))
      (node (ref "SV9") (pin "1") (pinfunction "1_1") (pintype "passive"))
    )
    (net (code "110") (name "P403") (class "Default")
      (node (ref "IC4") (pin "37") (pinfunction "RC3/AN15/SCK/SCL_37") (pintype "bidirectional"))
      (node (ref "SV9") (pin "3") (pinfunction "3_3") (pintype "passive"))
    )
    (net (code "111") (name "P404") (class "Default")
      (node (ref "IC4") (pin "36") (pinfunction "RC2/AN14/CCP1_36") (pintype "bidirectional"))
      (node (ref "SV9") (pin "4") (pinfunction "4_4") (pintype "passive"))
    )
    (net (code "112") (name "P405") (class "Default")
      (node (ref "IC4") (pin "39") (pinfunction "RD1/AN21_39") (pintype "bidirectional"))
      (node (ref "SV9") (pin "5") (pinfunction "5_5") (pintype "passive"))
    )
    (net (code "113") (name "P406") (class "Default")
      (node (ref "IC4") (pin "38") (pinfunction "RD0/AN20_38") (pintype "bidirectional"))
      (node (ref "SV9") (pin "6") (pinfunction "6_6") (pintype "passive"))
    )
    (net (code "114") (name "P407") (class "Default")
      (node (ref "IC4") (pin "41") (pinfunction "RD3/AN23_41") (pintype "bidirectional"))
      (node (ref "SV9") (pin "7") (pinfunction "7_7") (pintype "passive"))
    )
    (net (code "115") (name "P408") (class "Default")
      (node (ref "IC4") (pin "40") (pinfunction "RD2/AN22_40") (pintype "bidirectional"))
      (node (ref "SV9") (pin "8") (pinfunction "8_8") (pintype "passive"))
    )
    (net (code "116") (name "P409") (class "Default")
      (node (ref "IC4") (pin "43") (pinfunction "RC5/AN17/SDO_43") (pintype "bidirectional"))
      (node (ref "SV9") (pin "9") (pinfunction "9_9") (pintype "passive"))
    )
    (net (code "117") (name "P410") (class "Default")
      (node (ref "IC4") (pin "42") (pinfunction "RC4/AN16/SDI/SDA_42") (pintype "bidirectional"))
      (node (ref "SV9") (pin "10") (pinfunction "10_10") (pintype "passive"))
    )
    (net (code "118") (name "P411") (class "Default")
      (node (ref "IC4") (pin "1") (pinfunction "DT/RX/AN19/RC7_1") (pintype "bidirectional"))
      (node (ref "SV9") (pin "11") (pinfunction "11_11") (pintype "passive"))
    )
    (net (code "119") (name "P412") (class "Default")
      (node (ref "IC4") (pin "44") (pinfunction "RC6/AN18/TX/CK_44") (pintype "bidirectional"))
      (node (ref "SV9") (pin "12") (pinfunction "12_12") (pintype "passive"))
    )
    (net (code "120") (name "P413") (class "Default")
      (node (ref "IC4") (pin "3") (pinfunction "AN25/RD5_3") (pintype "bidirectional"))
      (node (ref "SV9") (pin "13") (pinfunction "13_13") (pintype "passive"))
    )
    (net (code "121") (name "P414") (class "Default")
      (node (ref "IC4") (pin "2") (pinfunction "AN24/RD4_2") (pintype "bidirectional"))
      (node (ref "SV9") (pin "14") (pinfunction "14_14") (pintype "passive"))
    )
    (net (code "122") (name "P415") (class "Default")
      (node (ref "IC4") (pin "5") (pinfunction "AN27/RD7_5") (pintype "bidirectional"))
      (node (ref "SV9") (pin "15") (pinfunction "15_15") (pintype "passive"))
    )
    (net (code "123") (name "P416") (class "Default")
      (node (ref "IC4") (pin "4") (pinfunction "AN26/RD6_4") (pintype "bidirectional"))
      (node (ref "SV9") (pin "16") (pinfunction "16_16") (pintype "passive"))
    )
    (net (code "124") (name "P417") (class "Default")
      (node (ref "IC4") (pin "9") (pinfunction "AN10/RB1_9") (pintype "bidirectional"))
      (node (ref "SV9") (pin "17") (pinfunction "17_17") (pintype "passive"))
    )
    (net (code "125") (name "P418") (class "Default")
      (node (ref "IC4") (pin "8") (pinfunction "INT/AN12/RB0_8") (pintype "bidirectional"))
      (node (ref "SV9") (pin "18") (pinfunction "18_18") (pintype "passive"))
    )
    (net (code "126") (name "P419") (class "Default")
      (node (ref "IC4") (pin "11") (pinfunction "CCP2/AN9/RB3_11") (pintype "bidirectional"))
      (node (ref "SV9") (pin "19") (pinfunction "19_19") (pintype "passive"))
    )
    (net (code "127") (name "P420") (class "Default")
      (node (ref "IC4") (pin "10") (pinfunction "AN8/RB2_10") (pintype "bidirectional"))
      (node (ref "SV9") (pin "20") (pinfunction "20_20") (pintype "passive"))
    )
    (net (code "128") (name "P421") (class "Default")
      (node (ref "IC4") (pin "14") (pinfunction "AN11/RB4_14") (pintype "bidirectional"))
      (node (ref "SV10") (pin "1") (pinfunction "1_1") (pintype "passive"))
    )
    (net (code "129") (name "P422") (class "Default")
      (node (ref "IC4") (pin "15") (pinfunction "T1G/AN13/RB5_15") (pintype "bidirectional"))
      (node (ref "SV10") (pin "2") (pinfunction "2_2") (pintype "passive"))
    )
    (net (code "130") (name "P425") (class "Default")
      (node (ref "IC4") (pin "19") (pinfunction "~{SS}/AN0/RA0_19") (pintype "bidirectional"))
      (node (ref "SV10") (pin "5") (pinfunction "5_5") (pintype "passive"))
    )
    (net (code "131") (name "P426") (class "Default")
      (node (ref "IC4") (pin "20") (pinfunction "AN1/RA1_20") (pintype "bidirectional"))
      (node (ref "SV10") (pin "6") (pinfunction "6_6") (pintype "passive"))
    )
    (net (code "132") (name "P427") (class "Default")
      (node (ref "IC4") (pin "21") (pinfunction "AN2/RA2_21") (pintype "bidirectional"))
      (node (ref "SV10") (pin "7") (pinfunction "7_7") (pintype "passive"))
    )
    (net (code "133") (name "P428") (class "Default")
      (node (ref "IC4") (pin "22") (pinfunction "VREF+/AN3/RA3_22") (pintype "bidirectional"))
      (node (ref "SV10") (pin "8") (pinfunction "8_8") (pintype "passive"))
    )
    (net (code "134") (name "P429") (class "Default")
      (node (ref "IC4") (pin "23") (pinfunction "RA4/TOCKI_23") (pintype "bidirectional"))
      (node (ref "SJ3") (pin "2") (pinfunction "2_2") (pintype "passive"))
      (node (ref "SV10") (pin "9") (pinfunction "9_9") (pintype "passive"))
    )
    (net (code "135") (name "P430") (class "Default")
      (node (ref "IC4") (pin "24") (pinfunction "RA5/AN4/~{SS}/VCAP_24") (pintype "bidirectional"))
      (node (ref "SV10") (pin "10") (pinfunction "10_10") (pintype "passive"))
    )
    (net (code "136") (name "P431") (class "Default")
      (node (ref "IC4") (pin "25") (pinfunction "RE0/AN5_25") (pintype "bidirectional"))
      (node (ref "SV10") (pin "11") (pinfunction "11_11") (pintype "passive"))
    )
    (net (code "137") (name "P432") (class "Default")
      (node (ref "IC4") (pin "26") (pinfunction "RE1/AN6_26") (pintype "bidirectional"))
      (node (ref "SV10") (pin "12") (pinfunction "12_12") (pintype "passive"))
    )
    (net (code "138") (name "P433") (class "Default")
      (node (ref "IC4") (pin "27") (pinfunction "RE2/AN7_27") (pintype "bidirectional"))
      (node (ref "SV10") (pin "13") (pinfunction "13_13") (pintype "passive"))
    )
    (net (code "139") (name "P436") (class "Default")
      (node (ref "IC4") (pin "32") (pinfunction "RC0/SOSCO/T1CKI_32") (pintype "bidirectional"))
      (node (ref "SV10") (pin "16") (pinfunction "16_16") (pintype "passive"))
    )
    (net (code "140") (name "P502") (class "Default")
      (node (ref "SV11") (pin "2") (pinfunction "2_2") (pintype "passive"))
    )
    (net (code "141") (name "P504") (class "Default")
      (node (ref "SV11") (pin "4") (pinfunction "4_4") (pintype "passive"))
    )
    (net (code "142") (name "P506") (class "Default")
      (node (ref "SV11") (pin "6") (pinfunction "6_6") (pintype "passive"))
    )
    (net (code "143") (name "P507") (class "Default")
      (node (ref "IC6") (pin "3") (pinfunction "3_3") (pintype "passive"))
      (node (ref "SV11") (pin "7") (pinfunction "7_7") (pintype "passive"))
    )
    (net (code "144") (name "P508") (class "Default")
      (node (ref "SV11") (pin "8") (pinfunction "8_8") (pintype "passive"))
    )
    (net (code "145") (name "P513") (class "Default")
      (node (ref "IC2") (pin "5") (pinfunction "5_5") (pintype "passive"))
      (node (ref "SV11") (pin "13") (pinfunction "13_13") (pintype "passive"))
    )
    (net (code "146") (name "P514") (class "Default")
      (node (ref "SV11") (pin "14") (pinfunction "14_14") (pintype "passive"))
    )
    (net (code "147") (name "P516") (class "Default")
      (node (ref "SV11") (pin "16") (pinfunction "16_16") (pintype "passive"))
    )
    (net (code "148") (name "P517") (class "Default")
      (node (ref "IC2") (pin "3") (pinfunction "3_3") (pintype "passive"))
      (node (ref "SV11") (pin "17") (pinfunction "17_17") (pintype "passive"))
    )
    (net (code "149") (name "P518") (class "Default")
      (node (ref "IC2") (pin "2") (pinfunction "2_2") (pintype "passive"))
      (node (ref "SV11") (pin "18") (pinfunction "18_18") (pintype "passive"))
    )
    (net (code "150") (name "P521") (class "Default")
      (node (ref "IC5") (pin "8") (pinfunction "8_8") (pintype "passive"))
      (node (ref "SV12") (pin "1") (pinfunction "1_1") (pintype "passive"))
    )
    (net (code "151") (name "P522") (class "Default")
      (node (ref "IC5") (pin "7") (pinfunction "7_7") (pintype "passive"))
      (node (ref "SV12") (pin "2") (pinfunction "2_2") (pintype "passive"))
    )
    (net (code "152") (name "P523") (class "Default")
      (node (ref "IC5") (pin "9") (pinfunction "9_9") (pintype "passive"))
      (node (ref "SV12") (pin "3") (pinfunction "3_3") (pintype "passive"))
    )
    (net (code "153") (name "P524") (class "Default")
      (node (ref "IC5") (pin "6") (pinfunction "6_6") (pintype "passive"))
      (node (ref "SV12") (pin "4") (pinfunction "4_4") (pintype "passive"))
    )
    (net (code "154") (name "P525") (class "Default")
      (node (ref "IC5") (pin "10") (pinfunction "10_10") (pintype "passive"))
      (node (ref "SV12") (pin "5") (pinfunction "5_5") (pintype "passive"))
    )
    (net (code "155") (name "P526") (class "Default")
      (node (ref "IC5") (pin "5") (pinfunction "5_5") (pintype "passive"))
      (node (ref "SV12") (pin "6") (pinfunction "6_6") (pintype "passive"))
    )
    (net (code "156") (name "P527") (class "Default")
      (node (ref "IC5") (pin "11") (pinfunction "11_11") (pintype "passive"))
      (node (ref "SV12") (pin "7") (pinfunction "7_7") (pintype "passive"))
    )
    (net (code "157") (name "P533") (class "Default")
      (node (ref "SV12") (pin "13") (pinfunction "13_13") (pintype "passive"))
    )
    (net (code "158") (name "P534") (class "Default")
      (node (ref "SV12") (pin "14") (pinfunction "14_14") (pintype "passive"))
    )
    (net (code "159") (name "P535") (class "Default")
      (node (ref "SV12") (pin "15") (pinfunction "15_15") (pintype "passive"))
    )
    (net (code "160") (name "P536") (class "Default")
      (node (ref "SV12") (pin "16") (pinfunction "16_16") (pintype "passive"))
    )
    (net (code "161") (name "PGC") (class "Default")
      (node (ref "IC1") (pin "17") (pinfunction "RB6_17") (pintype "bidirectional"))
      (node (ref "JP4") (pin "5") (pinfunction "5_5") (pintype "passive"))
      (node (ref "SV2") (pin "11") (pinfunction "11_11") (pintype "passive"))
    )
    (net (code "162") (name "PGD") (class "Default")
      (node (ref "IC1") (pin "18") (pinfunction "RB7_18") (pintype "bidirectional"))
      (node (ref "JP4") (pin "4") (pinfunction "4_4") (pintype "passive"))
      (node (ref "SV2") (pin "12") (pinfunction "12_12") (pintype "passive"))
    )
    (net (code "163") (name "VCAP") (class "Default")
      (node (ref "IC1") (pin "56") (pinfunction "VDDCORE_56") (pintype "power_in"))
      (node (ref "JMP1") (pin "2") (pinfunction "2_2") (pintype "passive"))
    )
    (net (code "164") (name "VCC") (class "Default")
      (node (ref "C10") (pin "1") (pinfunction "1_1") (pintype "passive"))
      (node (ref "C11") (pin "1") (pinfunction "1_1") (pintype "passive"))
      (node (ref "C12") (pin "1") (pinfunction "1_1") (pintype "passive"))
      (node (ref "C2") (pin "1") (pinfunction "1_1") (pintype "passive"))
      (node (ref "C25") (pin "+") (pinfunction "+_+") (pintype "passive"))
      (node (ref "C27") (pin "1") (pinfunction "1_1") (pintype "passive"))
      (node (ref "C28") (pin "1") (pinfunction "1_1") (pintype "passive"))
      (node (ref "C3") (pin "1") (pinfunction "1_1") (pintype "passive"))
      (node (ref "C32") (pin "1") (pinfunction "1_1") (pintype "passive"))
      (node (ref "C35") (pin "1") (pinfunction "1_1") (pintype "passive"))
      (node (ref "C36") (pin "1") (pinfunction "1_1") (pintype "passive"))
      (node (ref "C6") (pin "1") (pinfunction "1_1") (pintype "passive"))
      (node (ref "C7") (pin "1") (pinfunction "1_1") (pintype "passive"))
      (node (ref "C8") (pin "1") (pinfunction "1_1") (pintype "passive"))
      (node (ref "IC1") (pin "10") (pinfunction "VDD_10") (pintype "power_in"))
      (node (ref "IC1") (pin "19") (pinfunction "AVDD_19") (pintype "power_in"))
      (node (ref "IC1") (pin "26") (pinfunction "VDD_26") (pintype "power_in"))
      (node (ref "IC1") (pin "38") (pinfunction "VDD_38") (pintype "power_in"))
      (node (ref "IC2") (pin "1") (pinfunction "1_1") (pintype "passive"))
      (node (ref "IC3") (pin "17") (pinfunction "AVDD_17") (pintype "power_in"))
      (node (ref "IC3") (pin "28") (pinfunction "VDD_28") (pintype "power_in"))
      (node (ref "IC3") (pin "40") (pinfunction "VDD_40") (pintype "power_in"))
      (node (ref "IC4") (pin "28") (pinfunction "VDD_28") (pintype "power_in"))
      (node (ref "IC4") (pin "7") (pinfunction "VDD_7") (pintype "power_in"))
      (node (ref "IC5") (pin "1") (pinfunction "1_1") (pintype "passive"))
      (node (ref "IC6") (pin "2") (pinfunction "2_2") (pintype "passive"))
      (node (ref "JMP2") (pin "1") (pinfunction "1_1") (pintype "passive"))
      (node (ref "JP1") (pin "2") (pinfunction "2_2") (pintype "passive"))
      (node (ref "JP2") (pin "2") (pinfunction "2_2") (pintype "passive"))
      (node (ref "JP3") (pin "2") (pinfunction "2_2") (pintype "passive"))
      (node (ref "JP4") (pin "2") (pinfunction "2_2") (pintype "passive"))
      (node (ref "R1") (pin "2") (pinfunction "2_2") (pintype "passive"))
      (node (ref "R2") (pin "2") (pinfunction "2_2") (pintype "passive"))
      (node (ref "R3") (pin "2") (pinfunction "2_2") (pintype "passive"))
      (node (ref "R4") (pin "2") (pinfunction "2_2") (pintype "passive"))
      (node (ref "R6") (pin "2") (pinfunction "2_2") (pintype "passive"))
      (node (ref "R7") (pin "2") (pinfunction "2_2") (pintype "passive"))
      (node (ref "R8") (pin "2") (pinfunction "2_2") (pintype "passive"))
      (node (ref "R9") (pin "2") (pinfunction "2_2") (pintype "passive"))
      (node (ref "SJ3") (pin "1") (pinfunction "1_1") (pintype "passive"))
      (node (ref "SJ4") (pin "2") (pinfunction "2_2") (pintype "passive"))
      (node (ref "SV1") (pin "17") (pinfunction "17_17") (pintype "passive"))
      (node (ref "SV1") (pin "18") (pinfunction "18_18") (pintype "passive"))
      (node (ref "SV10") (pin "17") (pinfunction "17_17") (pintype "passive"))
      (node (ref "SV10") (pin "18") (pinfunction "18_18") (pintype "passive"))
      (node (ref "SV11") (pin "10") (pinfunction "10_10") (pintype "passive"))
      (node (ref "SV11") (pin "19") (pinfunction "19_19") (pintype "passive"))
      (node (ref "SV11") (pin "20") (pinfunction "20_20") (pintype "passive"))
      (node (ref "SV11") (pin "9") (pinfunction "9_9") (pintype "passive"))
      (node (ref "SV12") (pin "17") (pinfunction "17_17") (pintype "passive"))
      (node (ref "SV12") (pin "18") (pinfunction "18_18") (pintype "passive"))
      (node (ref "SV2") (pin "10") (pinfunction "10_10") (pintype "passive"))
      (node (ref "SV2") (pin "9") (pinfunction "9_9") (pintype "passive"))
      (node (ref "SV5") (pin "17") (pinfunction "17_17") (pintype "passive"))
      (node (ref "SV5") (pin "18") (pinfunction "18_18") (pintype "passive"))
    )
    (net (code "165") (name "VREG") (class "Default")
      (node (ref "IC1") (pin "57") (pinfunction "VREG_57") (pintype "passive"))
      (node (ref "JMP2") (pin "2") (pinfunction "2_2") (pintype "passive"))
    )
    (net (code "166") (name "VSS") (class "Default")
      (node (ref "C1") (pin "-") (pinfunction "-_-") (pintype "passive"))
      (node (ref "C10") (pin "2") (pinfunction "2_2") (pintype "passive"))
      (node (ref "C11") (pin "2") (pinfunction "2_2") (pintype "passive"))
      (node (ref "C12") (pin "2") (pinfunction "2_2") (pintype "passive"))
      (node (ref "C13") (pin "2") (pinfunction "2_2") (pintype "passive"))
      (node (ref "C14") (pin "2") (pinfunction "2_2") (pintype "passive"))
      (node (ref "C2") (pin "2") (pinfunction "2_2") (pintype "passive"))
      (node (ref "C25") (pin "-") (pinfunction "-_-") (pintype "passive"))
      (node (ref "C26") (pin "2") (pinfunction "2_2") (pintype "passive"))
      (node (ref "C27") (pin "2") (pinfunction "2_2") (pintype "passive"))
      (node (ref "C28") (pin "2") (pinfunction "2_2") (pintype "passive"))
      (node (ref "C29") (pin "2") (pinfunction "2_2") (pintype "passive"))
      (node (ref "C3") (pin "2") (pinfunction "2_2") (pintype "passive"))
      (node (ref "C30") (pin "2") (pinfunction "2_2") (pintype "passive"))
      (node (ref "C31") (pin "2") (pinfunction "2_2") (pintype "passive"))
      (node (ref "C32") (pin "2") (pinfunction "2_2") (pintype "passive"))
      (node (ref "C33") (pin "2") (pinfunction "2_2") (pintype "passive"))
      (node (ref "C34") (pin "2") (pinfunction "2_2") (pintype "passive"))
      (node (ref "C35") (pin "2") (pinfunction "2_2") (pintype "passive"))
      (node (ref "C36") (pin "2") (pinfunction "2_2") (pintype "passive"))
      (node (ref "C4") (pin "2") (pinfunction "2_2") (pintype "passive"))
      (node (ref "C5") (pin "2") (pinfunction "2_2") (pintype "passive"))
      (node (ref "C6") (pin "2") (pinfunction "2_2") (pintype "passive"))
      (node (ref "C7") (pin "2") (pinfunction "2_2") (pintype "passive"))
      (node (ref "C8") (pin "2") (pinfunction "2_2") (pintype "passive"))
      (node (ref "C9") (pin "-") (pinfunction "-_-") (pintype "passive"))
      (node (ref "C9B") (pin "2") (pinfunction "2_2") (pintype "passive"))
      (node (ref "IC1") (pin "20") (pinfunction "AVSS_20") (pintype "power_in"))
      (node (ref "IC1") (pin "25") (pinfunction "VSS_25") (pintype "power_in"))
      (node (ref "IC1") (pin "41") (pinfunction "VSS_41") (pintype "power_in"))
      (node (ref "IC1") (pin "9") (pinfunction "VSS_9") (pintype "power_in"))
      (node (ref "IC2") (pin "8") (pinfunction "8_8") (pintype "passive"))
      (node (ref "IC3") (pin "16") (pinfunction "AVSS_16") (pintype "power_in"))
      (node (ref "IC3") (pin "29") (pinfunction "VSS_29") (pintype "power_in"))
      (node (ref "IC3") (pin "39") (pinfunction "VSS_39") (pintype "power_in"))
      (node (ref "IC3") (pin "6") (pinfunction "DISVREG_6") (pintype "passive"))
      (node (ref "IC4") (pin "29") (pinfunction "VSS_29") (pintype "power_in"))
      (node (ref "IC4") (pin "6") (pinfunction "VSS_6") (pintype "power_in"))
      (node (ref "IC5") (pin "14") (pinfunction "14_14") (pintype "passive"))
      (node (ref "IC6") (pin "7") (pinfunction "7_7") (pintype "passive"))
      (node (ref "JMP1") (pin "3") (pinfunction "3_3") (pintype "passive"))
      (node (ref "JMP2") (pin "3") (pinfunction "3_3") (pintype "passive"))
      (node (ref "JP1") (pin "3") (pinfunction "3_3") (pintype "passive"))
      (node (ref "JP2") (pin "3") (pinfunction "3_3") (pintype "passive"))
      (node (ref "JP3") (pin "3") (pinfunction "3_3") (pintype "passive"))
      (node (ref "JP4") (pin "3") (pinfunction "3_3") (pintype "passive"))
      (node (ref "LED1") (pin "C") (pinfunction "C_C") (pintype "passive"))
      (node (ref "LED2") (pin "C") (pinfunction "C_C") (pintype "passive"))
      (node (ref "LED4") (pin "C") (pinfunction "C_C") (pintype "passive"))
      (node (ref "LED5") (pin "C") (pinfunction "C_C") (pintype "passive"))
      (node (ref "S1") (pin "3") (pinfunction "P_3") (pintype "passive"))
      (node (ref "S2") (pin "3") (pinfunction "P_3") (pintype "passive"))
      (node (ref "S4") (pin "3") (pinfunction "P_3") (pintype "passive"))
      (node (ref "S5") (pin "3") (pinfunction "P_3") (pintype "passive"))
      (node (ref "SV1") (pin "19") (pinfunction "19_19") (pintype "passive"))
      (node (ref "SV1") (pin "20") (pinfunction "20_20") (pintype "passive"))
      (node (ref "SV10") (pin "19") (pinfunction "19_19") (pintype "passive"))
      (node (ref "SV10") (pin "20") (pinfunction "20_20") (pintype "passive"))
      (node (ref "SV12") (pin "19") (pinfunction "19_19") (pintype "passive"))
      (node (ref "SV12") (pin "20") (pinfunction "20_20") (pintype "passive"))
      (node (ref "SV5") (pin "19") (pinfunction "19_19") (pintype "passive"))
      (node (ref "SV5") (pin "20") (pinfunction "20_20") (pintype "passive"))
    )
    (net (code "167") (name "unconnected-(S1-P1-Pad4)") (class "Default")
      (node (ref "S1") (pin "4") (pinfunction "P1_4") (pintype "passive"))
    )
    (net (code "168") (name "unconnected-(S1-S1-Pad2)") (class "Default")
      (node (ref "S1") (pin "2") (pinfunction "S1_2") (pintype "passive"))
    )
    (net (code "169") (name "unconnected-(S2-P1-Pad4)") (class "Default")
      (node (ref "S2") (pin "4") (pinfunction "P1_4") (pintype "passive"))
    )
    (net (code "170") (name "unconnected-(S2-S1-Pad2)") (class "Default")
      (node (ref "S2") (pin "2") (pinfunction "S1_2") (pintype "passive"))
    )
    (net (code "171") (name "unconnected-(S4-P1-Pad4)") (class "Default")
      (node (ref "S4") (pin "4") (pinfunction "P1_4") (pintype "passive"))
    )
    (net (code "172") (name "unconnected-(S4-S1-Pad2)") (class "Default")
      (node (ref "S4") (pin "2") (pinfunction "S1_2") (pintype "passive"))
    )
    (net (code "173") (name "unconnected-(S5-P1-Pad4)") (class "Default")
      (node (ref "S5") (pin "4") (pinfunction "P1_4") (pintype "passive"))
    )
    (net (code "174") (name "unconnected-(S5-S1-Pad2)") (class "Default")
      (node (ref "S5") (pin "2") (pinfunction "S1_2") (pintype "passive"))
    )
  )
)
